# ESP32C3.net
KiCad netlist of a schematic drawn in Altium Designer
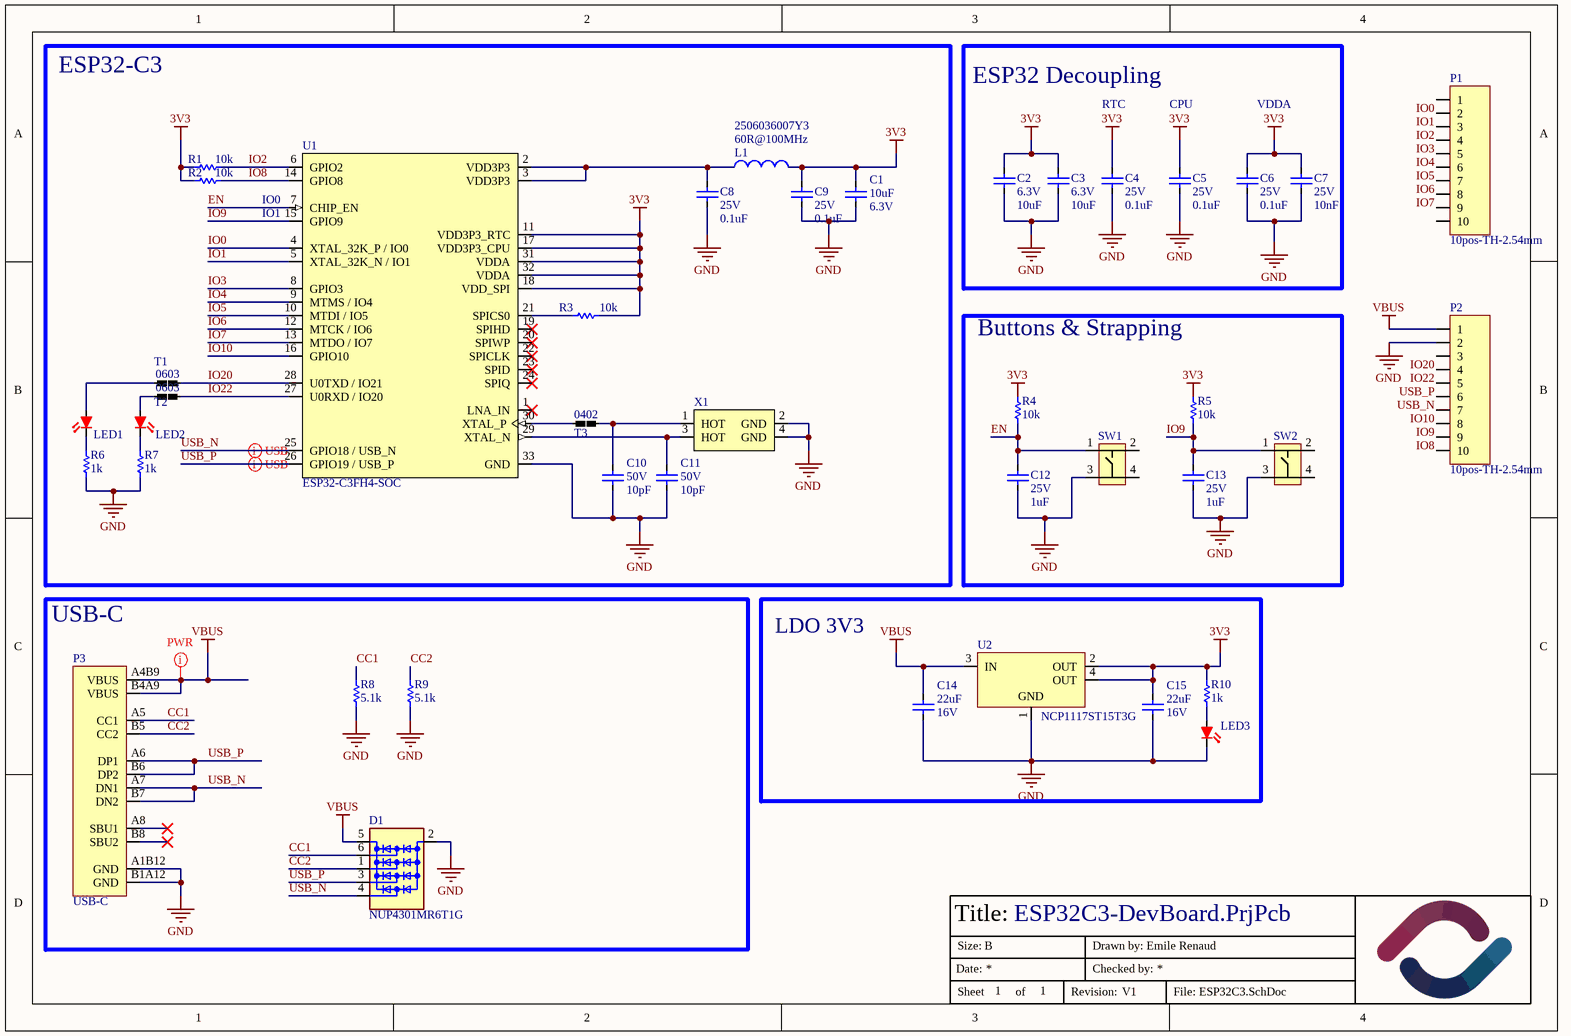
[diagram p0: ESP32C3.SchDoc]

(export (version "E")
  (design (tool "Eeschema 10.0.6"))
  (components
    (comp (ref "C1")
      (value "10uF")
      (footprint "CAPACITOR-0603")
      (description "Capacitor-0603-10uF-6.3V-X5R, Low ESR, Low ESL")
      (fields (field (name "VOLT") "6.3V") (field (name "Comment") "Capacitor-0603-10uF-6.3V-X5R"))
      (libsource (lib "Capacitors") (part "Capacitor-0603-10uF-6.3V-X5R"))
    )
    (comp (ref "C2")
      (value "10uF")
      (footprint "CAPACITOR-0603")
      (description "Capacitor-0603-10uF-6.3V-X5R, Low ESR, Low ESL")
      (fields (field (name "VOLT") "6.3V") (field (name "Comment") "Capacitor-0603-10uF-6.3V-X5R"))
      (libsource (lib "Capacitors") (part "Capacitor-0603-10uF-6.3V-X5R"))
    )
    (comp (ref "C3")
      (value "10uF")
      (footprint "CAPACITOR-0603")
      (description "Capacitor-0603-10uF-6.3V-X5R, Low ESR, Low ESL")
      (fields (field (name "VOLT") "6.3V") (field (name "Comment") "Capacitor-0603-10uF-6.3V-X5R"))
      (libsource (lib "Capacitors") (part "Capacitor-0603-10uF-6.3V-X5R"))
    )
    (comp (ref "C4")
      (value "0.1uF")
      (footprint "CAPACITOR-0402")
      (description "Capacitor-0402-0.1uF-25V-X5R")
      (fields (field (name "VOLT") "25V"))
      (libsource (lib "Capacitors") (part "Capacitor-0402-0.1uF-25V-X5R"))
    )
    (comp (ref "C5")
      (value "0.1uF")
      (footprint "CAPACITOR-0402")
      (description "Capacitor-0402-0.1uF-25V-X5R")
      (fields (field (name "VOLT") "25V"))
      (libsource (lib "Capacitors") (part "Capacitor-0402-0.1uF-25V-X5R"))
    )
    (comp (ref "C6")
      (value "0.1uF")
      (footprint "CAPACITOR-0402")
      (description "Capacitor-0402-0.1uF-25V-X5R")
      (fields (field (name "VOLT") "25V"))
      (libsource (lib "Capacitors") (part "Capacitor-0402-0.1uF-25V-X5R"))
    )
    (comp (ref "C7")
      (value "10nF")
      (footprint "CAPACITOR-0402")
      (description "Capacitor-0402-10nF-25V-X7R")
      (fields (field (name "VOLT") "25V"))
      (libsource (lib "Capacitors") (part "Capacitor-0402-10nF-25V-X7R"))
    )
    (comp (ref "C8")
      (value "0.1uF")
      (footprint "CAPACITOR-0402")
      (description "Capacitor-0402-0.1uF-25V-X5R")
      (fields (field (name "VOLT") "25V"))
      (libsource (lib "Capacitors") (part "Capacitor-0402-0.1uF-25V-X5R"))
    )
    (comp (ref "C9")
      (value "0.1uF")
      (footprint "CAPACITOR-0402")
      (description "Capacitor-0402-0.1uF-25V-X5R")
      (fields (field (name "VOLT") "25V"))
      (libsource (lib "Capacitors") (part "Capacitor-0402-0.1uF-25V-X5R"))
    )
    (comp (ref "C10")
      (value "10pF")
      (footprint "CAPACITOR-0402")
      (description "Capacitor-0402-10pF-50V-C0G")
      (fields (field (name "VOLT") "50V"))
      (libsource (lib "Capacitors") (part "Capacitor-0402-10pF-50V-C0G"))
    )
    (comp (ref "C11")
      (value "10pF")
      (footprint "CAPACITOR-0402")
      (description "Capacitor-0402-10pF-50V-C0G")
      (fields (field (name "VOLT") "50V"))
      (libsource (lib "Capacitors") (part "Capacitor-0402-10pF-50V-C0G"))
    )
    (comp (ref "C12")
      (value "1uF")
      (footprint "CAPACITOR-0603")
      (description "Capacitor-0603-1uF-25V-X5R")
      (fields (field (name "VOLT") "25V"))
      (libsource (lib "Capacitors") (part "Capacitor-0603-1uF-25V-X5R"))
    )
    (comp (ref "C13")
      (value "1uF")
      (footprint "CAPACITOR-0603")
      (description "Capacitor-0603-1uF-25V-X5R")
      (fields (field (name "VOLT") "25V"))
      (libsource (lib "Capacitors") (part "Capacitor-0603-1uF-25V-X5R"))
    )
    (comp (ref "C14")
      (value "22uF")
      (footprint "CAPACITOR-0805")
      (description "Capacitor-0805-22uF-16V-X5R")
      (fields (field (name "VOLT") "16V"))
      (libsource (lib "Capacitors") (part "Capacitor-0805-22uF-16V-X5R"))
    )
    (comp (ref "C15")
      (value "22uF")
      (footprint "CAPACITOR-0805")
      (description "Capacitor-0805-22uF-16V-X5R")
      (fields (field (name "VOLT") "16V"))
      (libsource (lib "Capacitors") (part "Capacitor-0805-22uF-16V-X5R"))
    )
    (comp (ref "D1")
      (value "NUP4301MR6T1G")
      (footprint "SOT-23-6")
      (description "4CH Clamp Ipp Tvs Diode Surface Mount SOT23-6 (SC74)")
      (libsource (lib "diodes") (part "NUP4301MR6T1G"))
    )
    (comp (ref "L1")
      (value "2506036007Y3")
      (footprint "CAPACITOR-0603")
      (description "60 Ohms @ 100 MHz 1 Signal Line Ferrite Bead 0603 (1608 Metric) 3A 40mOhm")
      (fields (field (name "ALTIUM_VALUE") "60R@100MHz"))
      (libsource (lib "Inductors") (part "2506036007Y3"))
    )
    (comp (ref "LED1")
      (value "B1911USD-20D000114U1930")
      (footprint "LED-0603-2PIN")
      (description "LED RED CLEAR 1608 SMD")
      (libsource (lib "LEDs") (part "B1911USD-20D000114U1930"))
    )
    (comp (ref "LED2")
      (value "B1911USD-20D000114U1930")
      (footprint "LED-0603-2PIN")
      (description "LED RED CLEAR 1608 SMD")
      (libsource (lib "LEDs") (part "B1911USD-20D000114U1930"))
    )
    (comp (ref "LED3")
      (value "B1911USD-20D000114U1930")
      (footprint "LED-0603-2PIN")
      (description "LED RED CLEAR 1608 SMD")
      (libsource (lib "LEDs") (part "B1911USD-20D000114U1930"))
    )
    (comp (ref "P1")
      (value "10pos-TH-2.54mm")
      (footprint "HDR1X10")
      (description "10pos TH 2.54mm Header")
      (libsource (lib "Header") (part "10pos-TH-2.54mm"))
    )
    (comp (ref "P2")
      (value "10pos-TH-2.54mm")
      (footprint "HDR1X10")
      (description "10pos TH 2.54mm Header")
      (libsource (lib "Header") (part "10pos-TH-2.54mm"))
    )
    (comp (ref "P3")
      (value "USB-C")
      (footprint "USB-C")
      (description "TYPEC-304J-BCP16\r\n5A USB 3.1 1 Type-C SMD USB Connectors")
      (libsource (lib "PC-connector") (part "USB-C"))
    )
    (comp (ref "R1")
      (value "10k")
      (footprint "Resistor-0402")
      (description "Resistor-0402-10k")
      (fields (field (name "Comment") "SMT resistor"))
      (libsource (lib "Resistors") (part "Resistor-0402-10k"))
    )
    (comp (ref "R2")
      (value "10k")
      (footprint "Resistor-0402")
      (description "Resistor-0402-10k")
      (fields (field (name "Comment") "SMT resistor"))
      (libsource (lib "Resistors") (part "Resistor-0402-10k"))
    )
    (comp (ref "R3")
      (value "10k")
      (footprint "Resistor-0402")
      (description "Resistor-0402-10k")
      (fields (field (name "Comment") "SMT resistor"))
      (libsource (lib "Resistors") (part "Resistor-0402-10k"))
    )
    (comp (ref "R4")
      (value "10k")
      (footprint "Resistor-0603")
      (description "Resistor0603-10k")
      (fields (field (name "Comment") "SMT resistor"))
      (libsource (lib "Resistors") (part "Resistor0603-10k"))
    )
    (comp (ref "R5")
      (value "10k")
      (footprint "Resistor-0603")
      (description "Resistor0603-10k")
      (fields (field (name "Comment") "SMT resistor"))
      (libsource (lib "Resistors") (part "Resistor0603-10k"))
    )
    (comp (ref "R6")
      (value "1k")
      (footprint "Resistor-0603")
      (description "Resistor0603-1k")
      (fields (field (name "Comment") "SMT resistor"))
      (libsource (lib "Resistors") (part "Resistor-0603-1k"))
    )
    (comp (ref "R7")
      (value "1k")
      (footprint "Resistor-0603")
      (description "Resistor0603-1k")
      (fields (field (name "Comment") "SMT resistor"))
      (libsource (lib "Resistors") (part "Resistor-0603-1k"))
    )
    (comp (ref "R8")
      (value "5.1k")
      (footprint "Resistor-0603")
      (description "Resistor-0603-5.1k")
      (fields (field (name "Comment") "SMT resistor"))
      (libsource (lib "Resistors") (part "Resistor-0603-5.1k"))
    )
    (comp (ref "R9")
      (value "5.1k")
      (footprint "Resistor-0603")
      (description "Resistor-0603-5.1k")
      (fields (field (name "Comment") "SMT resistor"))
      (libsource (lib "Resistors") (part "Resistor-0603-5.1k"))
    )
    (comp (ref "R10")
      (value "1k")
      (footprint "Resistor-0603")
      (description "Resistor0603-1k")
      (fields (field (name "Comment") "SMT resistor"))
      (libsource (lib "Resistors") (part "Resistor-0603-1k"))
    )
    (comp (ref "SW1")
      (value "PTS815 SJM 250 SMTR LFS")
      (footprint "SW4_PTS815 SJM 250 SMTR LFS_CNK")
      (description "TACT 4.2 X 3.2, 2.5 MM H, 180GF,")
      (libsource (lib "THTPushButtonSwitches") (part "PTS815 SJM 250 SMTR LFS"))
    )
    (comp (ref "SW2")
      (value "PTS815 SJM 250 SMTR LFS")
      (footprint "SW4_PTS815 SJM 250 SMTR LFS_CNK")
      (description "TACT 4.2 X 3.2, 2.5 MM H, 180GF,")
      (libsource (lib "THTPushButtonSwitches") (part "PTS815 SJM 250 SMTR LFS"))
    )
    (comp (ref "T1")
      (value "NetTie_0603_Short")
      (footprint "NetTie-0603-short")
      (libsource (lib "JumpersAndHoles") (part "NetTie_0603_Short"))
    )
    (comp (ref "T2")
      (value "NetTie_0603_Short")
      (footprint "NetTie-0603-short")
      (libsource (lib "JumpersAndHoles") (part "NetTie_0603_Short"))
    )
    (comp (ref "T3")
      (value "NetTie_0402")
      (footprint "NetTie-0402")
      (libsource (lib "JumpersAndHoles") (part "NetTie_0402"))
    )
    (comp (ref "U1")
      (value "ESP32-C3FH4-SOC")
      (footprint "VQFN-32-Exposed Pad")
      (fields (field (name "MF") "Espressif Systems") (field (name "MP") "ESP32-C3FH4"))
      (libsource (lib "Microcontrollers") (part "ESP32-C3FH4-SOC"))
    )
    (comp (ref "U2")
      (value "NCP1117ST15T3G")
      (footprint "SOT-223-3/TO-261-3S")
      (description "IC REG LINEAR 3.3V 1A SOT223")
      (libsource (lib "PMIC-VoltageRegulators-LinearRegulators") (part "NCP1117ST15T3G"))
    )
    (comp (ref "X1")
      (value "CX2016DB40000D0FLJCC")
      (footprint "4-SMD")
      (description "40 MHz ±10ppm Crystal 8pF 50 Ohms 4-SMD, No Lead")
      (libsource (lib "Crystals") (part "CX2016DB40000D0FLJCC"))
    )
  )
  (nets
    (net (code "1") (name "/CC1") (class "Default")
      (node (ref "D1") (pin "6") (pinfunction "L1_6") (pintype "passive"))
      (node (ref "P3") (pin "A5") (pinfunction "CC1_A5") (pintype "passive"))
      (node (ref "R8") (pin "2") (pinfunction "2_2") (pintype "passive"))
    )
    (net (code "2") (name "/CC2") (class "Default")
      (node (ref "D1") (pin "1") (pinfunction "L2_1") (pintype "passive"))
      (node (ref "P3") (pin "B5") (pinfunction "CC2_B5") (pintype "passive"))
      (node (ref "R9") (pin "2") (pinfunction "2_2") (pintype "passive"))
    )
    (net (code "3") (name "/EN") (class "Default")
      (node (ref "C12") (pin "2") (pinfunction "2_2") (pintype "passive"))
      (node (ref "R4") (pin "1") (pinfunction "1_1") (pintype "passive"))
      (node (ref "SW1") (pin "1") (pinfunction "1_1") (pintype "passive"))
      (node (ref "U1") (pin "7") (pinfunction "CHIP_EN_7") (pintype "input"))
    )
    (net (code "4") (name "/IO0") (class "Default")
      (node (ref "P1") (pin "1") (pinfunction "1_1") (pintype "passive"))
      (node (ref "U1") (pin "4") (pinfunction "XTAL_32K_P_/_IO0_4") (pintype "bidirectional"))
    )
    (net (code "5") (name "/IO1") (class "Default")
      (node (ref "P1") (pin "2") (pinfunction "2_2") (pintype "passive"))
      (node (ref "U1") (pin "5") (pinfunction "XTAL_32K_N_/_IO1_5") (pintype "bidirectional"))
    )
    (net (code "6") (name "/IO2") (class "Default")
      (node (ref "P1") (pin "3") (pinfunction "3_3") (pintype "passive"))
      (node (ref "R1") (pin "2") (pinfunction "2_2") (pintype "passive"))
      (node (ref "U1") (pin "6") (pinfunction "GPIO2_6") (pintype "bidirectional"))
    )
    (net (code "7") (name "/IO3") (class "Default")
      (node (ref "P1") (pin "4") (pinfunction "4_4") (pintype "passive"))
      (node (ref "U1") (pin "8") (pinfunction "GPIO3_8") (pintype "bidirectional"))
    )
    (net (code "8") (name "/IO4") (class "Default")
      (node (ref "P1") (pin "5") (pinfunction "5_5") (pintype "passive"))
      (node (ref "U1") (pin "9") (pinfunction "MTMS_/_IO4_9") (pintype "bidirectional"))
    )
    (net (code "9") (name "/IO5") (class "Default")
      (node (ref "P1") (pin "6") (pinfunction "6_6") (pintype "passive"))
      (node (ref "U1") (pin "10") (pinfunction "MTDI_/_IO5_10") (pintype "bidirectional"))
    )
    (net (code "10") (name "/IO6") (class "Default")
      (node (ref "P1") (pin "7") (pinfunction "7_7") (pintype "passive"))
      (node (ref "U1") (pin "12") (pinfunction "MTCK_/_IO6_12") (pintype "bidirectional"))
    )
    (net (code "11") (name "/IO7") (class "Default")
      (node (ref "P1") (pin "8") (pinfunction "8_8") (pintype "passive"))
      (node (ref "U1") (pin "13") (pinfunction "MTDO_/_IO7_13") (pintype "bidirectional"))
    )
    (net (code "12") (name "/IO8") (class "Default")
      (node (ref "P2") (pin "9") (pinfunction "9_9") (pintype "passive"))
      (node (ref "R2") (pin "2") (pinfunction "2_2") (pintype "passive"))
      (node (ref "U1") (pin "14") (pinfunction "GPIO8_14") (pintype "bidirectional"))
    )
    (net (code "13") (name "/IO9") (class "Default")
      (node (ref "C13") (pin "2") (pinfunction "2_2") (pintype "passive"))
      (node (ref "P2") (pin "8") (pinfunction "8_8") (pintype "passive"))
      (node (ref "R5") (pin "1") (pinfunction "1_1") (pintype "passive"))
      (node (ref "SW2") (pin "1") (pinfunction "1_1") (pintype "passive"))
      (node (ref "U1") (pin "15") (pinfunction "GPIO9_15") (pintype "bidirectional"))
    )
    (net (code "14") (name "/IO10") (class "Default")
      (node (ref "P2") (pin "7") (pinfunction "7_7") (pintype "passive"))
      (node (ref "U1") (pin "16") (pinfunction "GPIO10_16") (pintype "bidirectional"))
    )
    (net (code "15") (name "/IO20") (class "Default")
      (node (ref "P2") (pin "3") (pinfunction "3_3") (pintype "passive"))
      (node (ref "T1") (pin "1") (pinfunction "1_1") (pintype "passive"))
      (node (ref "U1") (pin "28") (pinfunction "U0TXD_/_IO21_28") (pintype "bidirectional"))
    )
    (net (code "16") (name "/IO22") (class "Default")
      (node (ref "P2") (pin "4") (pinfunction "4_4") (pintype "passive"))
      (node (ref "T2") (pin "1") (pinfunction "1_1") (pintype "passive"))
      (node (ref "U1") (pin "27") (pinfunction "U0RXD_/_IO20_27") (pintype "bidirectional"))
    )
    (net (code "17") (name "/USB_N") (class "Default")
      (node (ref "D1") (pin "4") (pinfunction "L4_4") (pintype "passive"))
      (node (ref "P2") (pin "6") (pinfunction "6_6") (pintype "passive"))
      (node (ref "P3") (pin "A7") (pinfunction "DN1_A7") (pintype "passive"))
      (node (ref "P3") (pin "B7") (pinfunction "DN2_B7") (pintype "passive"))
      (node (ref "U1") (pin "25") (pinfunction "GPIO18_/_USB_N_25") (pintype "bidirectional"))
    )
    (net (code "18") (name "/USB_P") (class "Default")
      (node (ref "D1") (pin "3") (pinfunction "L3_3") (pintype "passive"))
      (node (ref "P2") (pin "5") (pinfunction "5_5") (pintype "passive"))
      (node (ref "P3") (pin "A6") (pinfunction "DP1_A6") (pintype "passive"))
      (node (ref "P3") (pin "B6") (pinfunction "DP2_B6") (pintype "passive"))
      (node (ref "U1") (pin "26") (pinfunction "GPIO19_/_USB_P_26") (pintype "bidirectional"))
    )
    (net (code "19") (name "3V3") (class "Default")
      (node (ref "C1") (pin "2") (pinfunction "2_2") (pintype "passive"))
      (node (ref "C15") (pin "2") (pinfunction "2_2") (pintype "passive"))
      (node (ref "C2") (pin "2") (pinfunction "2_2") (pintype "passive"))
      (node (ref "C3") (pin "2") (pinfunction "2_2") (pintype "passive"))
      (node (ref "C4") (pin "2") (pinfunction "2_2") (pintype "passive"))
      (node (ref "C5") (pin "2") (pinfunction "2_2") (pintype "passive"))
      (node (ref "C6") (pin "2") (pinfunction "2_2") (pintype "passive"))
      (node (ref "C7") (pin "2") (pinfunction "2_2") (pintype "passive"))
      (node (ref "C9") (pin "2") (pinfunction "2_2") (pintype "passive"))
      (node (ref "L1") (pin "2") (pinfunction "2_2") (pintype "passive"))
      (node (ref "R1") (pin "1") (pinfunction "1_1") (pintype "passive"))
      (node (ref "R10") (pin "2") (pinfunction "2_2") (pintype "passive"))
      (node (ref "R2") (pin "1") (pinfunction "1_1") (pintype "passive"))
      (node (ref "R3") (pin "2") (pinfunction "2_2") (pintype "passive"))
      (node (ref "R4") (pin "2") (pinfunction "2_2") (pintype "passive"))
      (node (ref "R5") (pin "2") (pinfunction "2_2") (pintype "passive"))
      (node (ref "U1") (pin "11") (pinfunction "VDD3P3_RTC_11") (pintype "power_in"))
      (node (ref "U1") (pin "17") (pinfunction "VDD3P3_CPU_17") (pintype "power_in"))
      (node (ref "U1") (pin "18") (pinfunction "VDD_SPI_18") (pintype "power_in"))
      (node (ref "U1") (pin "31") (pinfunction "VDDA_31") (pintype "power_in"))
      (node (ref "U1") (pin "32") (pinfunction "VDDA_32") (pintype "power_in"))
      (node (ref "U2") (pin "2") (pinfunction "OUT_2") (pintype "passive"))
      (node (ref "U2") (pin "4") (pinfunction "OUT_4") (pintype "passive"))
    )
    (net (code "20") (name "GND") (class "Default")
      (node (ref "C1") (pin "1") (pinfunction "1_1") (pintype "passive"))
      (node (ref "C10") (pin "1") (pinfunction "1_1") (pintype "passive"))
      (node (ref "C11") (pin "1") (pinfunction "1_1") (pintype "passive"))
      (node (ref "C12") (pin "1") (pinfunction "1_1") (pintype "passive"))
      (node (ref "C13") (pin "1") (pinfunction "1_1") (pintype "passive"))
      (node (ref "C14") (pin "1") (pinfunction "1_1") (pintype "passive"))
      (node (ref "C15") (pin "1") (pinfunction "1_1") (pintype "passive"))
      (node (ref "C2") (pin "1") (pinfunction "1_1") (pintype "passive"))
      (node (ref "C3") (pin "1") (pinfunction "1_1") (pintype "passive"))
      (node (ref "C4") (pin "1") (pinfunction "1_1") (pintype "passive"))
      (node (ref "C5") (pin "1") (pinfunction "1_1") (pintype "passive"))
      (node (ref "C6") (pin "1") (pinfunction "1_1") (pintype "passive"))
      (node (ref "C7") (pin "1") (pinfunction "1_1") (pintype "passive"))
      (node (ref "C8") (pin "1") (pinfunction "1_1") (pintype "passive"))
      (node (ref "C9") (pin "1") (pinfunction "1_1") (pintype "passive"))
      (node (ref "D1") (pin "2") (pinfunction "GND_2") (pintype "passive"))
      (node (ref "LED3") (pin "1") (pinfunction "K_1") (pintype "passive"))
      (node (ref "P2") (pin "2") (pinfunction "2_2") (pintype "passive"))
      (node (ref "P3") (pin "A1B12") (pinfunction "GND_A1B12") (pintype "passive"))
      (node (ref "P3") (pin "B1A12") (pinfunction "GND_B1A12") (pintype "passive"))
      (node (ref "R6") (pin "2") (pinfunction "2_2") (pintype "passive"))
      (node (ref "R7") (pin "2") (pinfunction "2_2") (pintype "passive"))
      (node (ref "R8") (pin "1") (pinfunction "1_1") (pintype "passive"))
      (node (ref "R9") (pin "1") (pinfunction "1_1") (pintype "passive"))
      (node (ref "SW1") (pin "3") (pinfunction "3_3") (pintype "passive"))
      (node (ref "SW2") (pin "3") (pinfunction "3_3") (pintype "passive"))
      (node (ref "U1") (pin "33") (pinfunction "GND_33") (pintype "power_in"))
      (node (ref "U2") (pin "1") (pinfunction "GND_1") (pintype "passive"))
      (node (ref "X1") (pin "2") (pinfunction "GND_2") (pintype "passive"))
      (node (ref "X1") (pin "4") (pinfunction "GND_4") (pintype "passive"))
    )
    (net (code "21") (name "Net-(C8-Pad2)") (class "Default")
      (node (ref "C8") (pin "2") (pinfunction "2_2") (pintype "passive"))
      (node (ref "L1") (pin "1") (pinfunction "1_1") (pintype "passive"))
      (node (ref "U1") (pin "2") (pinfunction "VDD3P3_2") (pintype "power_in"))
      (node (ref "U1") (pin "3") (pinfunction "VDD3P3_3") (pintype "power_in"))
    )
    (net (code "22") (name "Net-(C10-Pad2)") (class "Default")
      (node (ref "C10") (pin "2") (pinfunction "2_2") (pintype "passive"))
      (node (ref "T3") (pin "1") (pinfunction "1_1") (pintype "passive"))
      (node (ref "X1") (pin "1") (pinfunction "HOT_1") (pintype "passive"))
    )
    (net (code "23") (name "Net-(LED1-K)") (class "Default")
      (node (ref "LED1") (pin "1") (pinfunction "K_1") (pintype "passive"))
      (node (ref "R6") (pin "1") (pinfunction "1_1") (pintype "passive"))
    )
    (net (code "24") (name "Net-(LED1-R)") (class "Default")
      (node (ref "LED1") (pin "2") (pinfunction "R_2") (pintype "passive"))
      (node (ref "T1") (pin "2") (pinfunction "2_2") (pintype "passive"))
    )
    (net (code "25") (name "Net-(LED2-K)") (class "Default")
      (node (ref "LED2") (pin "1") (pinfunction "K_1") (pintype "passive"))
      (node (ref "R7") (pin "1") (pinfunction "1_1") (pintype "passive"))
    )
    (net (code "26") (name "Net-(LED2-R)") (class "Default")
      (node (ref "LED2") (pin "2") (pinfunction "R_2") (pintype "passive"))
      (node (ref "T2") (pin "2") (pinfunction "2_2") (pintype "passive"))
    )
    (net (code "27") (name "Net-(LED3-R)") (class "Default")
      (node (ref "LED3") (pin "2") (pinfunction "R_2") (pintype "passive"))
      (node (ref "R10") (pin "1") (pinfunction "1_1") (pintype "passive"))
    )
    (net (code "28") (name "Net-(U1-SPICS0)") (class "Default")
      (node (ref "R3") (pin "1") (pinfunction "1_1") (pintype "passive"))
      (node (ref "U1") (pin "21") (pinfunction "SPICS0_21") (pintype "bidirectional"))
    )
    (net (code "29") (name "Net-(U1-XTAL_N)") (class "Default")
      (node (ref "C11") (pin "2") (pinfunction "2_2") (pintype "passive"))
      (node (ref "U1") (pin "29") (pinfunction "XTAL_N_29") (pintype "output"))
      (node (ref "X1") (pin "3") (pinfunction "HOT_3") (pintype "passive"))
    )
    (net (code "30") (name "Net-(U1-XTAL_P)") (class "Default")
      (node (ref "T3") (pin "2") (pinfunction "2_2") (pintype "passive"))
      (node (ref "U1") (pin "30") (pinfunction "XTAL_P_30") (pintype "input"))
    )
    (net (code "31") (name "VBUS") (class "Default")
      (node (ref "C14") (pin "2") (pinfunction "2_2") (pintype "passive"))
      (node (ref "D1") (pin "5") (pinfunction "VDD_5") (pintype "passive"))
      (node (ref "P2") (pin "1") (pinfunction "1_1") (pintype "passive"))
      (node (ref "P3") (pin "A4B9") (pinfunction "VBUS_A4B9") (pintype "passive"))
      (node (ref "P3") (pin "B4A9") (pinfunction "VBUS_B4A9") (pintype "passive"))
      (node (ref "U2") (pin "3") (pinfunction "IN_3") (pintype "passive"))
    )
    (net (code "32") (name "unconnected-(P1-Pad9)") (class "Default")
      (node (ref "P1") (pin "9") (pinfunction "9_9") (pintype "passive"))
    )
    (net (code "33") (name "unconnected-(P1-Pad10)") (class "Default")
      (node (ref "P1") (pin "10") (pinfunction "10_10") (pintype "passive"))
    )
    (net (code "34") (name "unconnected-(P2-Pad10)") (class "Default")
      (node (ref "P2") (pin "10") (pinfunction "10_10") (pintype "passive"))
    )
    (net (code "35") (name "unconnected-(P3-SBU1-PadA8)") (class "Default")
      (node (ref "P3") (pin "A8") (pinfunction "SBU1_A8") (pintype "passive+no_connect"))
    )
    (net (code "36") (name "unconnected-(P3-SBU2-PadB8)") (class "Default")
      (node (ref "P3") (pin "B8") (pinfunction "SBU2_B8") (pintype "passive+no_connect"))
    )
    (net (code "37") (name "unconnected-(SW1-Pad2)") (class "Default")
      (node (ref "SW1") (pin "2") (pinfunction "2_2") (pintype "passive"))
    )
    (net (code "38") (name "unconnected-(SW1-Pad4)") (class "Default")
      (node (ref "SW1") (pin "4") (pinfunction "4_4") (pintype "passive"))
    )
    (net (code "39") (name "unconnected-(SW2-Pad2)") (class "Default")
      (node (ref "SW2") (pin "2") (pinfunction "2_2") (pintype "passive"))
    )
    (net (code "40") (name "unconnected-(SW2-Pad4)") (class "Default")
      (node (ref "SW2") (pin "4") (pinfunction "4_4") (pintype "passive"))
    )
    (net (code "41") (name "unconnected-(U1-LNA_IN-Pad1)") (class "Default")
      (node (ref "U1") (pin "1") (pinfunction "LNA_IN_1") (pintype "bidirectional+no_connect"))
    )
    (net (code "42") (name "unconnected-(U1-SPICLK-Pad22)") (class "Default")
      (node (ref "U1") (pin "22") (pinfunction "SPICLK_22") (pintype "bidirectional+no_connect"))
    )
    (net (code "43") (name "unconnected-(U1-SPID-Pad23)") (class "Default")
      (node (ref "U1") (pin "23") (pinfunction "SPID_23") (pintype "bidirectional+no_connect"))
    )
    (net (code "44") (name "unconnected-(U1-SPIHD-Pad19)") (class "Default")
      (node (ref "U1") (pin "19") (pinfunction "SPIHD_19") (pintype "bidirectional+no_connect"))
    )
    (net (code "45") (name "unconnected-(U1-SPIQ-Pad24)") (class "Default")
      (node (ref "U1") (pin "24") (pinfunction "SPIQ_24") (pintype "bidirectional+no_connect"))
    )
    (net (code "46") (name "unconnected-(U1-SPIWP-Pad20)") (class "Default")
      (node (ref "U1") (pin "20") (pinfunction "SPIWP_20") (pintype "bidirectional+no_connect"))
    )
  )
)
